# Schematic.net
KiCad netlist of a schematic drawn in Altium Designer
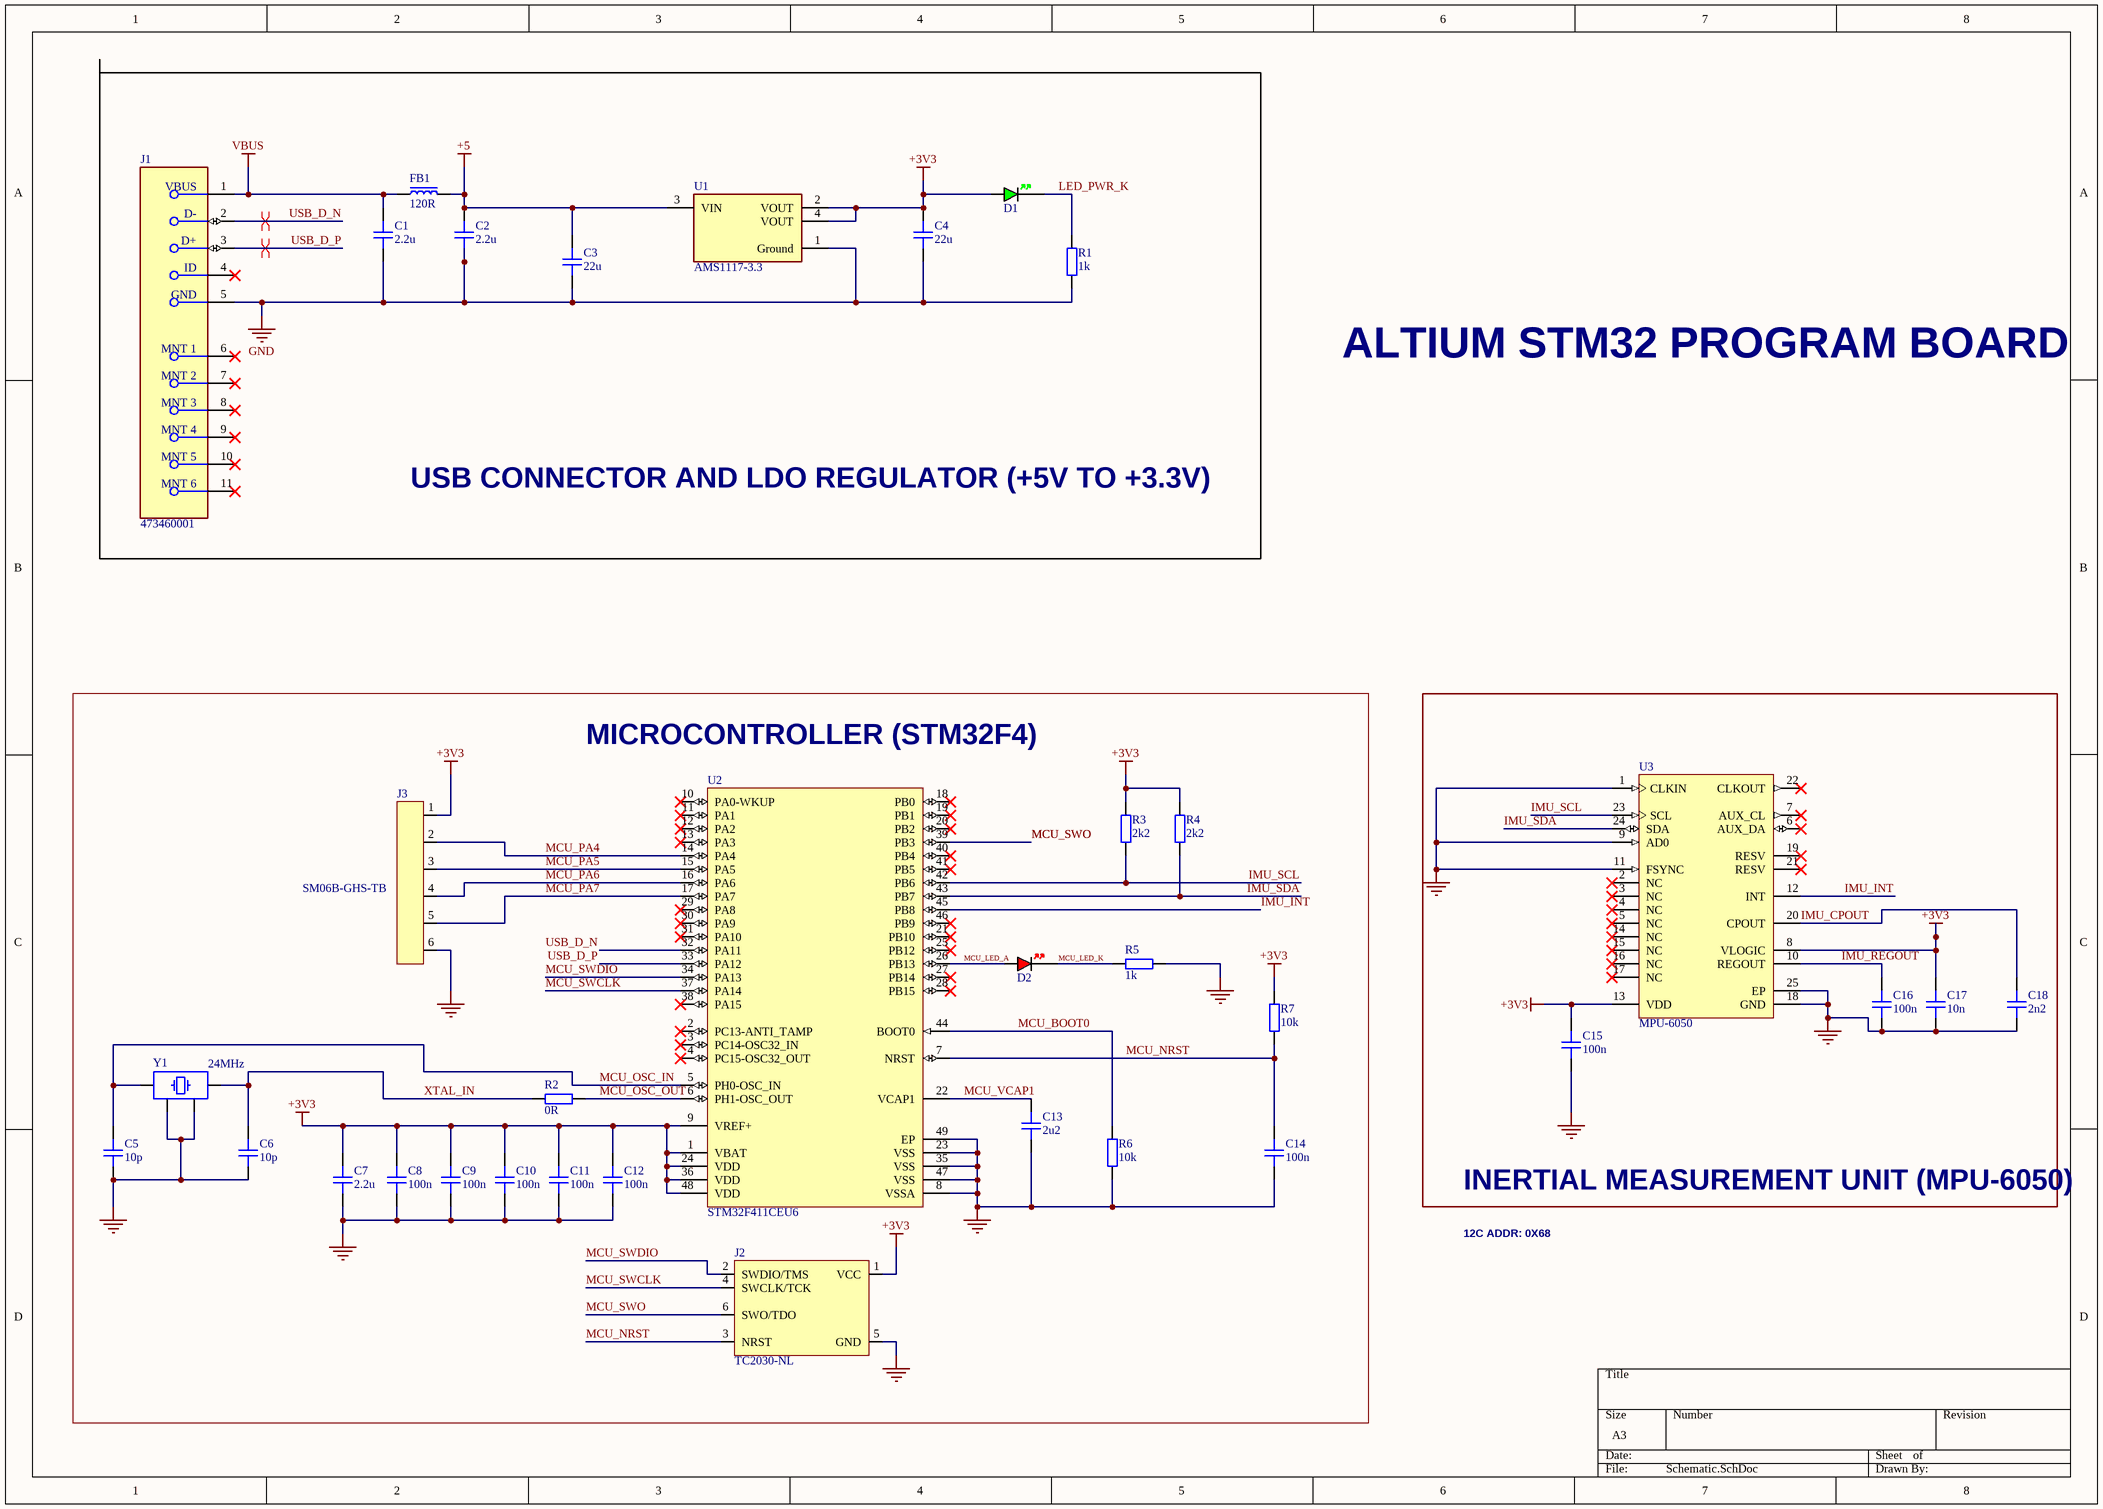
[diagram p0: Schematic.SchDoc]

(export (version "E")
  (design (tool "Eeschema 10.0.6"))
  (components
    (comp (ref "C1")
      (value "2.2u")
      (footprint "CAP_0603")
      (description "Capacitor SMD 0603")
      (libsource (lib "Schematic-Lib-PhilsLab") (part "CAP_0603"))
    )
    (comp (ref "C2")
      (value "2.2u")
      (footprint "CAP_0603")
      (description "Capacitor SMD 0603")
      (libsource (lib "Schematic-Lib-PhilsLab") (part "CAP_0603"))
    )
    (comp (ref "C3")
      (value "22u")
      (footprint "CAP_0805")
      (description "Capacitor SMD 0805")
      (libsource (lib "Schematic-Lib-PhilsLab") (part "CAP_0805"))
    )
    (comp (ref "C4")
      (value "22u")
      (footprint "CAP_0805")
      (description "Capacitor SMD 0805")
      (libsource (lib "Schematic-Lib-PhilsLab") (part "CAP_0805"))
    )
    (comp (ref "C5")
      (value "10p")
      (footprint "CAP_0402")
      (description "Capacitor SMD 0402")
      (libsource (lib "Schematic-Lib-PhilsLab") (part "CAP_0402"))
    )
    (comp (ref "C6")
      (value "10p")
      (footprint "CAP_0402")
      (description "Capacitor SMD 0402")
      (libsource (lib "Schematic-Lib-PhilsLab") (part "CAP_0402"))
    )
    (comp (ref "C7")
      (value "2.2u")
      (footprint "CAP_0603")
      (description "Capacitor SMD 0603")
      (libsource (lib "Schematic-Lib-PhilsLab") (part "CAP_0603"))
    )
    (comp (ref "C8")
      (value "100n")
      (footprint "CAP_0402")
      (description "Capacitor SMD 0402")
      (libsource (lib "Schematic-Lib-PhilsLab") (part "CAP_0402"))
    )
    (comp (ref "C9")
      (value "100n")
      (footprint "CAP_0402")
      (description "Capacitor SMD 0402")
      (libsource (lib "Schematic-Lib-PhilsLab") (part "CAP_0402"))
    )
    (comp (ref "C10")
      (value "100n")
      (footprint "CAP_0402")
      (description "Capacitor SMD 0402")
      (libsource (lib "Schematic-Lib-PhilsLab") (part "CAP_0402"))
    )
    (comp (ref "C11")
      (value "100n")
      (footprint "CAP_0402")
      (description "Capacitor SMD 0402")
      (libsource (lib "Schematic-Lib-PhilsLab") (part "CAP_0402"))
    )
    (comp (ref "C12")
      (value "100n")
      (footprint "CAP_0402")
      (description "Capacitor SMD 0402")
      (libsource (lib "Schematic-Lib-PhilsLab") (part "CAP_0402"))
    )
    (comp (ref "C13")
      (value "2u2")
      (footprint "CAP_0603")
      (description "Capacitor SMD 0603")
      (libsource (lib "Schematic-Lib-PhilsLab") (part "CAP_0603"))
    )
    (comp (ref "C14")
      (value "100n")
      (footprint "CAP_0402")
      (description "Capacitor SMD 0402")
      (libsource (lib "Schematic-Lib-PhilsLab") (part "CAP_0402"))
    )
    (comp (ref "C15")
      (value "100n")
      (footprint "CAP_0402")
      (description "Capacitor SMD 0402")
      (libsource (lib "Schematic-Lib-PhilsLab") (part "CAP_0402"))
    )
    (comp (ref "C16")
      (value "100n")
      (footprint "CAP_0402")
      (description "Capacitor SMD 0402")
      (libsource (lib "Schematic-Lib-PhilsLab") (part "CAP_0402"))
    )
    (comp (ref "C17")
      (value "10n")
      (footprint "CAP_0402")
      (description "Capacitor SMD 0402")
      (libsource (lib "Schematic-Lib-PhilsLab") (part "CAP_0402"))
    )
    (comp (ref "C18")
      (value "2n2")
      (footprint "CAP_0402")
      (description "Capacitor SMD 0402")
      (libsource (lib "Schematic-Lib-PhilsLab") (part "CAP_0402"))
    )
    (comp (ref "D1")
      (value "GREEN")
      (footprint "LED_0402_GREEN")
      (description "LED 0402 GREEN SMD")
      (libsource (lib "Schematic-Lib-PhilsLab") (part "LED_0402_GREEN"))
    )
    (comp (ref "D2")
      (value "RED")
      (footprint "LED_0402_RED")
      (description "LED 0402 RED SMD")
      (libsource (lib "Schematic-Lib-PhilsLab") (part "LED_0402_RED"))
    )
    (comp (ref "FB1")
      (value "120R")
      (footprint "FB_0603")
      (description "Ferrite Bead SMD 0603")
      (libsource (lib "Schematic-Lib-PhilsLab") (part "FB_0603"))
    )
    (comp (ref "J1")
      (value "473460001")
      (footprint "FP-473460001-MFG")
      (description "CONN RCPT USB2.0 MICRO B SMD R/A")
      (fields
        (field (name "OCTOPART") "https://octopart.com/47346-0001-molex-7164928")
        (field (name "MANUFACTURER") "Molex")
      )
      (libsource (lib "Altium Content Vault") (part "53ae1f1d9b557310b43ca686e5bb76a"))
    )
    (comp (ref "J2")
      (value "TC2030-NL")
      (footprint "TC2030-NL-FP")
      (description "Tag-Connect No-Solder SWD Debug Connector (No Legs) DO NOT PLACE")
      (fields
        (field (name "MANUFACTURER") "Tag-Connect")
        (field (name "MANUFACTURER PART NUMBER") "TC2030-NL-FP")
      )
      (libsource (lib "Schematic-Lib-PhilsLab") (part "TC2030-NL"))
    )
    (comp (ref "J3")
      (value "SM06B-GHS-TB")
      (footprint "SM06B-GHS-TB")
      (description "Header Connector 6 Position 1.25MM Pitch SMD Horizontal JST GH")
      (fields (field (name "MANUFACTURER") "JST"))
      (libsource (lib "Schematic-Lib-PhilsLab") (part "SM06B-GHS-TB"))
    )
    (comp (ref "R1")
      (value "1k")
      (footprint "RES_0402")
      (description "Resistor SMD 0402")
      (libsource (lib "Schematic-Lib-PhilsLab") (part "RES_0402"))
    )
    (comp (ref "R2")
      (value "0R")
      (footprint "RES_0402")
      (description "Resistor SMD 0402")
      (libsource (lib "Schematic-Lib-PhilsLab") (part "RES_0402"))
    )
    (comp (ref "R3")
      (value "2k2")
      (footprint "RES_0402")
      (description "Resistor SMD 0402")
      (libsource (lib "Schematic-Lib-PhilsLab") (part "RES_0402"))
    )
    (comp (ref "R4")
      (value "2k2")
      (footprint "RES_0402")
      (description "Resistor SMD 0402")
      (libsource (lib "Schematic-Lib-PhilsLab") (part "RES_0402"))
    )
    (comp (ref "R5")
      (value "1k")
      (footprint "RES_0402")
      (description "Resistor SMD 0402")
      (libsource (lib "Schematic-Lib-PhilsLab") (part "RES_0402"))
    )
    (comp (ref "R6")
      (value "10k")
      (footprint "RES_0402")
      (description "Resistor SMD 0402")
      (libsource (lib "Schematic-Lib-PhilsLab") (part "RES_0402"))
    )
    (comp (ref "R7")
      (value "10k")
      (footprint "RES_0402")
      (description "Resistor SMD 0402")
      (libsource (lib "Schematic-Lib-PhilsLab") (part "RES_0402"))
    )
    (comp (ref "U1")
      (value "AMS1117-3.3")
      (footprint "FP-AMS1117-IPC_C")
      (description "LDO Voltage Regulators 1A, 3.3V")
      (fields
        (field (name "OCTOPART") "https://octopart.com/ams1117-3.3-advanced+monolithic+systems-25899300")
        (field (name "MANUFACTURER") "Advanced Monolithic Systems")
      )
      (libsource (lib "Altium Content Vault") (part "8bdbb5f8e77002000e30dd2845d0354"))
    )
    (comp (ref "U2")
      (value "STM32F411CEU6")
      (footprint "STM-UFQFPN48_L")
      (libsource (lib "Altium Content Vault") (part "MC-ARM-STM32F411-UFQFPN48"))
    )
    (comp (ref "U3")
      (value "MPU-6050")
      (footprint "IS-QFN-24_V")
      (fields (field (name "MANUFACTURER") "InvenSense"))
      (libsource (lib "Altium Content Vault") (part "IS-MPU-6050-QFN-24"))
    )
    (comp (ref "Y1")
      (value "24MHz")
      (footprint "XTAL_3225")
      (description "Crystal SMD 24MHz 10PPM 7pF 3225")
      (fields
        (field (name "MANUFACTURER") "Epson")
        (field (name "MANUFACTURER PART NUMBER") "TSX-3225 24.0000MF15X-AC")
      )
      (libsource (lib "Schematic-Lib-PhilsLab") (part "TSX-3225_24.0000MF15X-AC"))
    )
  )
  (nets
    (net (code "1") (name "+3V3") (class "Default")
      (node (ref "C10") (pin "2") (pinfunction "2_2") (pintype "passive"))
      (node (ref "C11") (pin "2") (pinfunction "2_2") (pintype "passive"))
      (node (ref "C12") (pin "2") (pinfunction "2_2") (pintype "passive"))
      (node (ref "C15") (pin "2") (pinfunction "2_2") (pintype "passive"))
      (node (ref "C17") (pin "2") (pinfunction "2_2") (pintype "passive"))
      (node (ref "C4") (pin "2") (pinfunction "2_2") (pintype "passive"))
      (node (ref "C7") (pin "2") (pinfunction "2_2") (pintype "passive"))
      (node (ref "C8") (pin "2") (pinfunction "2_2") (pintype "passive"))
      (node (ref "C9") (pin "2") (pinfunction "2_2") (pintype "passive"))
      (node (ref "D1") (pin "A") (pinfunction "A_A") (pintype "passive"))
      (node (ref "J2") (pin "1") (pinfunction "VCC_1") (pintype "passive"))
      (node (ref "J3") (pin "1") (pinfunction "1_1") (pintype "passive"))
      (node (ref "R3") (pin "2") (pinfunction "2_2") (pintype "passive"))
      (node (ref "R4") (pin "2") (pinfunction "2_2") (pintype "passive"))
      (node (ref "R7") (pin "2") (pinfunction "2_2") (pintype "passive"))
      (node (ref "U1") (pin "2") (pinfunction "VOUT_2") (pintype "passive"))
      (node (ref "U1") (pin "4") (pinfunction "VOUT_4") (pintype "passive"))
      (node (ref "U2") (pin "1") (pinfunction "VBAT_1") (pintype "power_in"))
      (node (ref "U2") (pin "24") (pinfunction "VDD_24") (pintype "power_in"))
      (node (ref "U2") (pin "36") (pinfunction "VDD_36") (pintype "power_in"))
      (node (ref "U2") (pin "48") (pinfunction "VDD_48") (pintype "power_in"))
      (node (ref "U2") (pin "9") (pinfunction "VREF+_9") (pintype "power_in"))
      (node (ref "U3") (pin "13") (pinfunction "VDD_13") (pintype "power_in"))
      (node (ref "U3") (pin "8") (pinfunction "VLOGIC_8") (pintype "power_in"))
    )
    (net (code "2") (name "+5") (class "Default")
      (node (ref "C2") (pin "2") (pinfunction "2_2") (pintype "passive"))
      (node (ref "C3") (pin "2") (pinfunction "2_2") (pintype "passive"))
      (node (ref "FB1") (pin "2") (pinfunction "2_2") (pintype "passive"))
      (node (ref "U1") (pin "3") (pinfunction "VIN_3") (pintype "power_in"))
    )
    (net (code "3") (name "/IMU_CPOUT") (class "Default")
      (node (ref "C18") (pin "2") (pinfunction "2_2") (pintype "passive"))
      (node (ref "U3") (pin "20") (pinfunction "CPOUT_20") (pintype "passive"))
    )
    (net (code "4") (name "/IMU_INT") (class "Default")
      (node (ref "U2") (pin "45") (pinfunction "PB8_45") (pintype "bidirectional"))
      (node (ref "U3") (pin "12") (pinfunction "INT_12") (pintype "open_collector"))
    )
    (net (code "5") (name "/IMU_REGOUT") (class "Default")
      (node (ref "C16") (pin "2") (pinfunction "2_2") (pintype "passive"))
      (node (ref "U3") (pin "10") (pinfunction "REGOUT_10") (pintype "passive"))
    )
    (net (code "6") (name "/IMU_SCL") (class "Default")
      (node (ref "R3") (pin "1") (pinfunction "1_1") (pintype "passive"))
      (node (ref "U2") (pin "42") (pinfunction "PB6_42") (pintype "bidirectional"))
      (node (ref "U3") (pin "23") (pinfunction "SCL_23") (pintype "input"))
    )
    (net (code "7") (name "/IMU_SDA") (class "Default")
      (node (ref "R4") (pin "1") (pinfunction "1_1") (pintype "passive"))
      (node (ref "U2") (pin "43") (pinfunction "PB7_43") (pintype "bidirectional"))
      (node (ref "U3") (pin "24") (pinfunction "SDA_24") (pintype "bidirectional"))
    )
    (net (code "8") (name "/LED_PWR_K") (class "Default")
      (node (ref "D1") (pin "K") (pinfunction "K_K") (pintype "passive"))
      (node (ref "R1") (pin "2") (pinfunction "2_2") (pintype "passive"))
    )
    (net (code "9") (name "/MCU_BOOT0") (class "Default")
      (node (ref "R6") (pin "2") (pinfunction "2_2") (pintype "passive"))
      (node (ref "U2") (pin "44") (pinfunction "BOOT0_44") (pintype "input"))
    )
    (net (code "10") (name "/MCU_LED_A") (class "Default")
      (node (ref "D2") (pin "A") (pinfunction "A_A") (pintype "passive"))
      (node (ref "U2") (pin "26") (pinfunction "PB13_26") (pintype "bidirectional"))
    )
    (net (code "11") (name "/MCU_LED_K") (class "Default")
      (node (ref "D2") (pin "K") (pinfunction "K_K") (pintype "passive"))
      (node (ref "R5") (pin "2") (pinfunction "2_2") (pintype "passive"))
    )
    (net (code "12") (name "/MCU_NRST") (class "Default")
      (node (ref "C14") (pin "2") (pinfunction "2_2") (pintype "passive"))
      (node (ref "J2") (pin "3") (pinfunction "NRST_3") (pintype "passive"))
      (node (ref "R7") (pin "1") (pinfunction "1_1") (pintype "passive"))
      (node (ref "U2") (pin "7") (pinfunction "NRST_7") (pintype "bidirectional"))
    )
    (net (code "13") (name "/MCU_OSC_IN") (class "Default")
      (node (ref "C5") (pin "2") (pinfunction "2_2") (pintype "passive"))
      (node (ref "U2") (pin "5") (pinfunction "PH0-OSC_IN_5") (pintype "bidirectional"))
      (node (ref "Y1") (pin "1") (pinfunction "1_1") (pintype "passive"))
    )
    (net (code "14") (name "/MCU_OSC_OUT") (class "Default")
      (node (ref "R2") (pin "2") (pinfunction "2_2") (pintype "passive"))
      (node (ref "U2") (pin "6") (pinfunction "PH1-OSC_OUT_6") (pintype "bidirectional"))
    )
    (net (code "15") (name "/MCU_PA4") (class "Default")
      (node (ref "J3") (pin "2") (pinfunction "2_2") (pintype "passive"))
      (node (ref "U2") (pin "14") (pinfunction "PA4_14") (pintype "bidirectional"))
    )
    (net (code "16") (name "/MCU_PA5") (class "Default")
      (node (ref "J3") (pin "3") (pinfunction "3_3") (pintype "passive"))
      (node (ref "U2") (pin "15") (pinfunction "PA5_15") (pintype "bidirectional"))
    )
    (net (code "17") (name "/MCU_PA6") (class "Default")
      (node (ref "J3") (pin "4") (pinfunction "4_4") (pintype "passive"))
      (node (ref "U2") (pin "16") (pinfunction "PA6_16") (pintype "bidirectional"))
    )
    (net (code "18") (name "/MCU_PA7") (class "Default")
      (node (ref "J3") (pin "5") (pinfunction "5_5") (pintype "passive"))
      (node (ref "U2") (pin "17") (pinfunction "PA7_17") (pintype "bidirectional"))
    )
    (net (code "19") (name "/MCU_SWCLK") (class "Default")
      (node (ref "J2") (pin "4") (pinfunction "SWCLK/TCK_4") (pintype "passive"))
      (node (ref "U2") (pin "37") (pinfunction "PA14_37") (pintype "bidirectional"))
    )
    (net (code "20") (name "/MCU_SWDIO") (class "Default")
      (node (ref "J2") (pin "2") (pinfunction "SWDIO/TMS_2") (pintype "passive"))
      (node (ref "U2") (pin "34") (pinfunction "PA13_34") (pintype "bidirectional"))
    )
    (net (code "21") (name "/MCU_SWO") (class "Default")
      (node (ref "J2") (pin "6") (pinfunction "SWO/TDO_6") (pintype "passive"))
      (node (ref "U2") (pin "39") (pinfunction "PB3_39") (pintype "bidirectional"))
    )
    (net (code "22") (name "/MCU_VCAP1") (class "Default")
      (node (ref "C13") (pin "2") (pinfunction "2_2") (pintype "passive"))
      (node (ref "U2") (pin "22") (pinfunction "VCAP1_22") (pintype "passive"))
    )
    (net (code "23") (name "/USB_D_N") (class "Default")
      (node (ref "J1") (pin "2") (pinfunction "D-_2") (pintype "bidirectional"))
      (node (ref "U2") (pin "32") (pinfunction "PA11_32") (pintype "bidirectional"))
    )
    (net (code "24") (name "/USB_D_P") (class "Default")
      (node (ref "J1") (pin "3") (pinfunction "D+_3") (pintype "bidirectional"))
      (node (ref "U2") (pin "33") (pinfunction "PA12_33") (pintype "bidirectional"))
    )
    (net (code "25") (name "/XTAL_IN") (class "Default")
      (node (ref "C6") (pin "2") (pinfunction "2_2") (pintype "passive"))
      (node (ref "R2") (pin "1") (pinfunction "1_1") (pintype "passive"))
      (node (ref "Y1") (pin "3") (pinfunction "3_3") (pintype "passive"))
    )
    (net (code "26") (name "GND") (class "Default")
      (node (ref "C1") (pin "1") (pinfunction "1_1") (pintype "passive"))
      (node (ref "C10") (pin "1") (pinfunction "1_1") (pintype "passive"))
      (node (ref "C11") (pin "1") (pinfunction "1_1") (pintype "passive"))
      (node (ref "C12") (pin "1") (pinfunction "1_1") (pintype "passive"))
      (node (ref "C13") (pin "1") (pinfunction "1_1") (pintype "passive"))
      (node (ref "C14") (pin "1") (pinfunction "1_1") (pintype "passive"))
      (node (ref "C15") (pin "1") (pinfunction "1_1") (pintype "passive"))
      (node (ref "C16") (pin "1") (pinfunction "1_1") (pintype "passive"))
      (node (ref "C17") (pin "1") (pinfunction "1_1") (pintype "passive"))
      (node (ref "C18") (pin "1") (pinfunction "1_1") (pintype "passive"))
      (node (ref "C2") (pin "1") (pinfunction "1_1") (pintype "passive"))
      (node (ref "C3") (pin "1") (pinfunction "1_1") (pintype "passive"))
      (node (ref "C4") (pin "1") (pinfunction "1_1") (pintype "passive"))
      (node (ref "C5") (pin "1") (pinfunction "1_1") (pintype "passive"))
      (node (ref "C6") (pin "1") (pinfunction "1_1") (pintype "passive"))
      (node (ref "C7") (pin "1") (pinfunction "1_1") (pintype "passive"))
      (node (ref "C8") (pin "1") (pinfunction "1_1") (pintype "passive"))
      (node (ref "C9") (pin "1") (pinfunction "1_1") (pintype "passive"))
      (node (ref "J1") (pin "5") (pinfunction "GND_5") (pintype "power_in"))
      (node (ref "J2") (pin "5") (pinfunction "GND_5") (pintype "passive"))
      (node (ref "J3") (pin "6") (pinfunction "6_6") (pintype "passive"))
      (node (ref "R1") (pin "1") (pinfunction "1_1") (pintype "passive"))
      (node (ref "R5") (pin "1") (pinfunction "1_1") (pintype "passive"))
      (node (ref "R6") (pin "1") (pinfunction "1_1") (pintype "passive"))
      (node (ref "U1") (pin "1") (pinfunction "Ground_1") (pintype "power_in"))
      (node (ref "U2") (pin "23") (pinfunction "VSS_23") (pintype "power_in"))
      (node (ref "U2") (pin "35") (pinfunction "VSS_35") (pintype "power_in"))
      (node (ref "U2") (pin "47") (pinfunction "VSS_47") (pintype "power_in"))
      (node (ref "U2") (pin "49") (pinfunction "EP_49") (pintype "power_in"))
      (node (ref "U2") (pin "8") (pinfunction "VSSA_8") (pintype "power_in"))
      (node (ref "U3") (pin "1") (pinfunction "CLKIN_1") (pintype "input"))
      (node (ref "U3") (pin "11") (pinfunction "FSYNC_11") (pintype "input"))
      (node (ref "U3") (pin "18") (pinfunction "GND_18") (pintype "power_in"))
      (node (ref "U3") (pin "25") (pinfunction "EP_25") (pintype "power_in"))
      (node (ref "U3") (pin "9") (pinfunction "AD0_9") (pintype "input"))
      (node (ref "Y1") (pin "2") (pinfunction "2_2") (pintype "passive"))
      (node (ref "Y1") (pin "4") (pinfunction "4_4") (pintype "passive"))
    )
    (net (code "27") (name "VBUS") (class "Default")
      (node (ref "C1") (pin "2") (pinfunction "2_2") (pintype "passive"))
      (node (ref "FB1") (pin "1") (pinfunction "1_1") (pintype "passive"))
      (node (ref "J1") (pin "1") (pinfunction "VBUS_1") (pintype "power_in"))
    )
    (net (code "28") (name "unconnected-(J1-ID-Pad4)") (class "Default")
      (node (ref "J1") (pin "4") (pinfunction "ID_4") (pintype "passive+no_connect"))
    )
    (net (code "29") (name "unconnected-(J1-MNT_1-Pad6)") (class "Default")
      (node (ref "J1") (pin "6") (pinfunction "MNT_1_6") (pintype "passive+no_connect"))
    )
    (net (code "30") (name "unconnected-(J1-MNT_2-Pad7)") (class "Default")
      (node (ref "J1") (pin "7") (pinfunction "MNT_2_7") (pintype "passive+no_connect"))
    )
    (net (code "31") (name "unconnected-(J1-MNT_3-Pad8)") (class "Default")
      (node (ref "J1") (pin "8") (pinfunction "MNT_3_8") (pintype "passive+no_connect"))
    )
    (net (code "32") (name "unconnected-(J1-MNT_4-Pad9)") (class "Default")
      (node (ref "J1") (pin "9") (pinfunction "MNT_4_9") (pintype "passive+no_connect"))
    )
    (net (code "33") (name "unconnected-(J1-MNT_5-Pad10)") (class "Default")
      (node (ref "J1") (pin "10") (pinfunction "MNT_5_10") (pintype "passive+no_connect"))
    )
    (net (code "34") (name "unconnected-(J1-MNT_6-Pad11)") (class "Default")
      (node (ref "J1") (pin "11") (pinfunction "MNT_6_11") (pintype "passive+no_connect"))
    )
    (net (code "35") (name "unconnected-(U2-PA0-WKUP-Pad10)") (class "Default")
      (node (ref "U2") (pin "10") (pinfunction "PA0-WKUP_10") (pintype "bidirectional+no_connect"))
    )
    (net (code "36") (name "unconnected-(U2-PA1-Pad11)") (class "Default")
      (node (ref "U2") (pin "11") (pinfunction "PA1_11") (pintype "bidirectional+no_connect"))
    )
    (net (code "37") (name "unconnected-(U2-PA2-Pad12)") (class "Default")
      (node (ref "U2") (pin "12") (pinfunction "PA2_12") (pintype "bidirectional+no_connect"))
    )
    (net (code "38") (name "unconnected-(U2-PA3-Pad13)") (class "Default")
      (node (ref "U2") (pin "13") (pinfunction "PA3_13") (pintype "bidirectional+no_connect"))
    )
    (net (code "39") (name "unconnected-(U2-PA8-Pad29)") (class "Default")
      (node (ref "U2") (pin "29") (pinfunction "PA8_29") (pintype "bidirectional+no_connect"))
    )
    (net (code "40") (name "unconnected-(U2-PA9-Pad30)") (class "Default")
      (node (ref "U2") (pin "30") (pinfunction "PA9_30") (pintype "bidirectional+no_connect"))
    )
    (net (code "41") (name "unconnected-(U2-PA10-Pad31)") (class "Default")
      (node (ref "U2") (pin "31") (pinfunction "PA10_31") (pintype "bidirectional+no_connect"))
    )
    (net (code "42") (name "unconnected-(U2-PA15-Pad38)") (class "Default")
      (node (ref "U2") (pin "38") (pinfunction "PA15_38") (pintype "bidirectional+no_connect"))
    )
    (net (code "43") (name "unconnected-(U2-PB0-Pad18)") (class "Default")
      (node (ref "U2") (pin "18") (pinfunction "PB0_18") (pintype "bidirectional+no_connect"))
    )
    (net (code "44") (name "unconnected-(U2-PB1-Pad19)") (class "Default")
      (node (ref "U2") (pin "19") (pinfunction "PB1_19") (pintype "bidirectional+no_connect"))
    )
    (net (code "45") (name "unconnected-(U2-PB2-Pad20)") (class "Default")
      (node (ref "U2") (pin "20") (pinfunction "PB2_20") (pintype "bidirectional+no_connect"))
    )
    (net (code "46") (name "unconnected-(U2-PB4-Pad40)") (class "Default")
      (node (ref "U2") (pin "40") (pinfunction "PB4_40") (pintype "bidirectional+no_connect"))
    )
    (net (code "47") (name "unconnected-(U2-PB5-Pad41)") (class "Default")
      (node (ref "U2") (pin "41") (pinfunction "PB5_41") (pintype "bidirectional+no_connect"))
    )
    (net (code "48") (name "unconnected-(U2-PB9-Pad46)") (class "Default")
      (node (ref "U2") (pin "46") (pinfunction "PB9_46") (pintype "bidirectional+no_connect"))
    )
    (net (code "49") (name "unconnected-(U2-PB10-Pad21)") (class "Default")
      (node (ref "U2") (pin "21") (pinfunction "PB10_21") (pintype "bidirectional+no_connect"))
    )
    (net (code "50") (name "unconnected-(U2-PB12-Pad25)") (class "Default")
      (node (ref "U2") (pin "25") (pinfunction "PB12_25") (pintype "bidirectional+no_connect"))
    )
    (net (code "51") (name "unconnected-(U2-PB14-Pad27)") (class "Default")
      (node (ref "U2") (pin "27") (pinfunction "PB14_27") (pintype "bidirectional+no_connect"))
    )
    (net (code "52") (name "unconnected-(U2-PB15-Pad28)") (class "Default")
      (node (ref "U2") (pin "28") (pinfunction "PB15_28") (pintype "bidirectional+no_connect"))
    )
    (net (code "53") (name "unconnected-(U2-PC13-ANTI_TAMP-Pad2)") (class "Default")
      (node (ref "U2") (pin "2") (pinfunction "PC13-ANTI_TAMP_2") (pintype "bidirectional+no_connect"))
    )
    (net (code "54") (name "unconnected-(U2-PC14-OSC32_IN-Pad3)") (class "Default")
      (node (ref "U2") (pin "3") (pinfunction "PC14-OSC32_IN_3") (pintype "bidirectional+no_connect"))
    )
    (net (code "55") (name "unconnected-(U2-PC15-OSC32_OUT-Pad4)") (class "Default")
      (node (ref "U2") (pin "4") (pinfunction "PC15-OSC32_OUT_4") (pintype "bidirectional+no_connect"))
    )
    (net (code "56") (name "unconnected-(U3-AUX_CL-Pad7)") (class "Default")
      (node (ref "U3") (pin "7") (pinfunction "AUX_CL_7") (pintype "output+no_connect"))
    )
    (net (code "57") (name "unconnected-(U3-AUX_DA-Pad6)") (class "Default")
      (node (ref "U3") (pin "6") (pinfunction "AUX_DA_6") (pintype "bidirectional+no_connect"))
    )
    (net (code "58") (name "unconnected-(U3-CLKOUT-Pad22)") (class "Default")
      (node (ref "U3") (pin "22") (pinfunction "CLKOUT_22") (pintype "output+no_connect"))
    )
    (net (code "59") (name "unconnected-(U3-NC-Pad2)") (class "Default")
      (node (ref "U3") (pin "2") (pinfunction "NC_2") (pintype "passive+no_connect"))
    )
    (net (code "60") (name "unconnected-(U3-NC-Pad3)") (class "Default")
      (node (ref "U3") (pin "3") (pinfunction "NC_3") (pintype "passive+no_connect"))
    )
    (net (code "61") (name "unconnected-(U3-NC-Pad4)") (class "Default")
      (node (ref "U3") (pin "4") (pinfunction "NC_4") (pintype "passive+no_connect"))
    )
    (net (code "62") (name "unconnected-(U3-NC-Pad5)") (class "Default")
      (node (ref "U3") (pin "5") (pinfunction "NC_5") (pintype "passive+no_connect"))
    )
    (net (code "63") (name "unconnected-(U3-NC-Pad14)") (class "Default")
      (node (ref "U3") (pin "14") (pinfunction "NC_14") (pintype "passive+no_connect"))
    )
    (net (code "64") (name "unconnected-(U3-NC-Pad15)") (class "Default")
      (node (ref "U3") (pin "15") (pinfunction "NC_15") (pintype "passive+no_connect"))
    )
    (net (code "65") (name "unconnected-(U3-NC-Pad16)") (class "Default")
      (node (ref "U3") (pin "16") (pinfunction "NC_16") (pintype "passive+no_connect"))
    )
    (net (code "66") (name "unconnected-(U3-NC-Pad17)") (class "Default")
      (node (ref "U3") (pin "17") (pinfunction "NC_17") (pintype "passive+no_connect"))
    )
    (net (code "67") (name "unconnected-(U3-RESV-Pad19)") (class "Default")
      (node (ref "U3") (pin "19") (pinfunction "RESV_19") (pintype "passive+no_connect"))
    )
    (net (code "68") (name "unconnected-(U3-RESV-Pad21)") (class "Default")
      (node (ref "U3") (pin "21") (pinfunction "RESV_21") (pintype "passive+no_connect"))
    )
  )
)
